# QCopterRC_ETH_Sch.net
KiCad netlist of a schematic drawn in Altium Designer
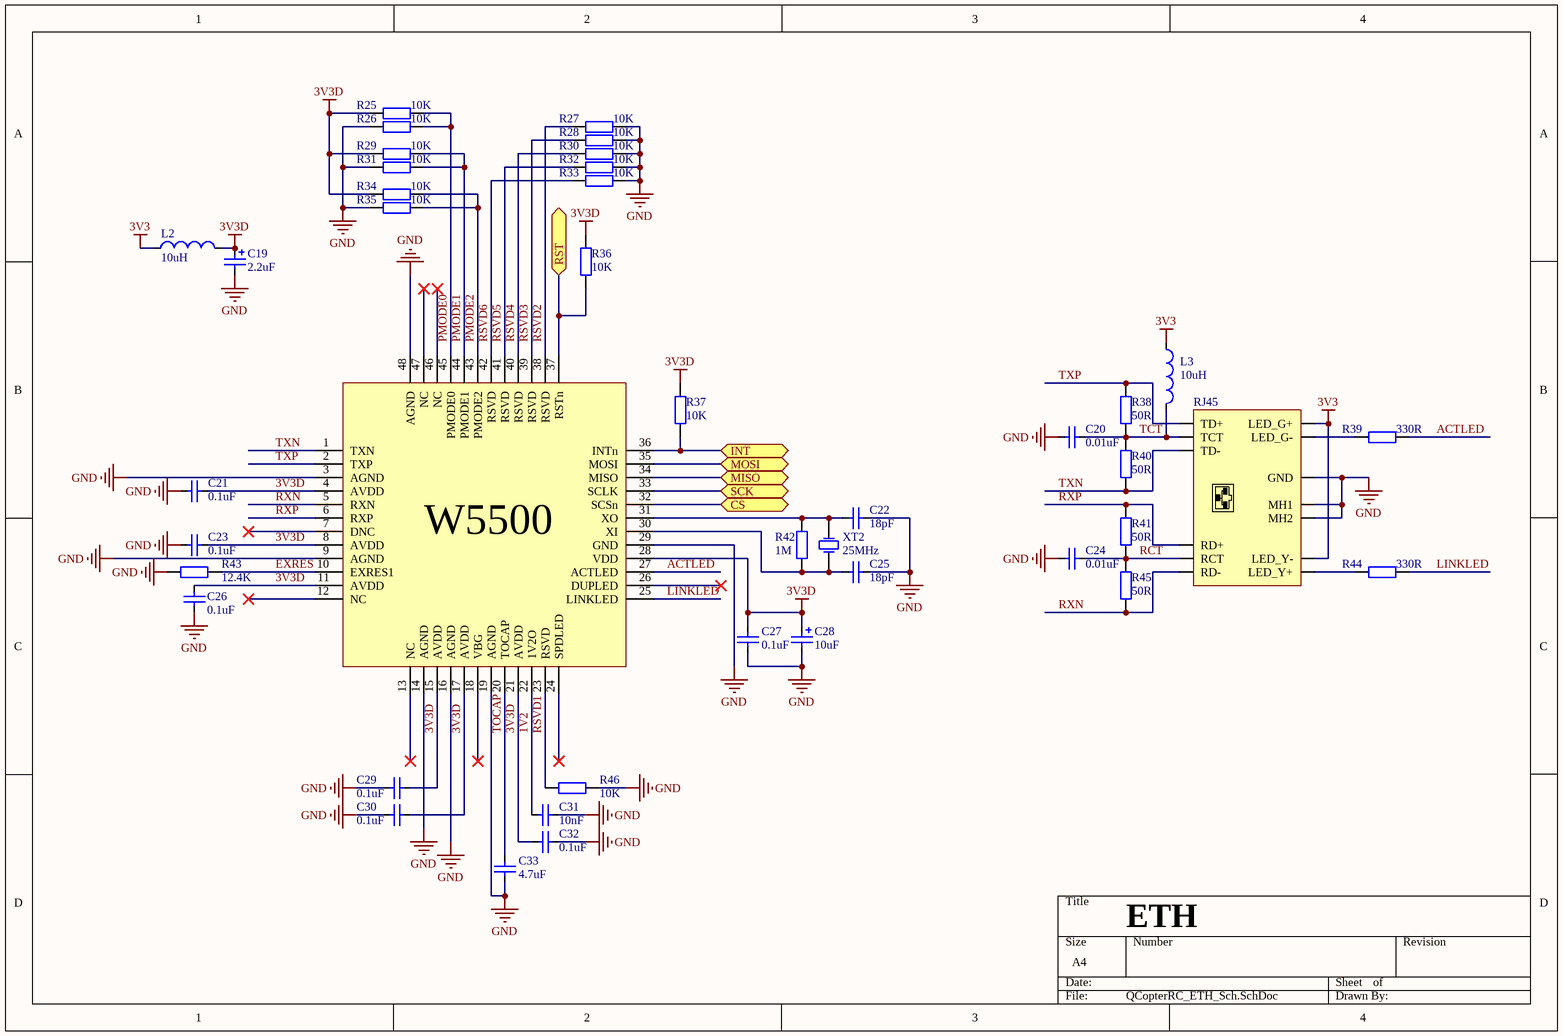
[diagram p0: QCopterRC_ETH_Sch.SchDoc]

(export (version "E")
  (design (tool "Eeschema 10.0.6"))
  (components
    (comp (ref "C19")
      (value "2.2uF")
      (footprint "PCB_Passive:CAP_TAN_P0805")
      (description "Capacitor")
      (fields (field (name "Comment") "Cap_Tan_0805"))
      (libsource (lib "SCH_Passive") (part "Cap_Tan_0805"))
    )
    (comp (ref "C20")
      (value "0.01uF")
      (footprint "PCB_Passive:CAP_0603")
      (description "Capacitor")
      (fields (field (name "Comment") "Cap_0603"))
      (libsource (lib "SCH_Passive") (part "Cap_0603"))
    )
    (comp (ref "C21")
      (value "0.1uF")
      (footprint "PCB_Passive:CAP_0603")
      (description "Capacitor")
      (fields (field (name "Comment") "Cap_0603"))
      (libsource (lib "SCH_Passive") (part "Cap_0603"))
    )
    (comp (ref "C22")
      (value "18pF")
      (footprint "PCB_Passive:CAP_0603")
      (description "Capacitor")
      (fields (field (name "Comment") "Cap_0603"))
      (libsource (lib "SCH_Passive") (part "Cap_0603"))
    )
    (comp (ref "C23")
      (value "0.1uF")
      (footprint "PCB_Passive:CAP_0603")
      (description "Capacitor")
      (fields (field (name "Comment") "Cap_0603"))
      (libsource (lib "SCH_Passive") (part "Cap_0603"))
    )
    (comp (ref "C24")
      (value "0.01uF")
      (footprint "PCB_Passive:CAP_0603")
      (description "Capacitor")
      (fields (field (name "Comment") "Cap_0603"))
      (libsource (lib "SCH_Passive") (part "Cap_0603"))
    )
    (comp (ref "C25")
      (value "18pF")
      (footprint "PCB_Passive:CAP_0603")
      (description "Capacitor")
      (fields (field (name "Comment") "Cap_0603"))
      (libsource (lib "SCH_Passive") (part "Cap_0603"))
    )
    (comp (ref "C26")
      (value "0.1uF")
      (footprint "PCB_Passive:CAP_0603")
      (description "Capacitor")
      (fields (field (name "Comment") "Cap_0603"))
      (libsource (lib "SCH_Passive") (part "Cap_0603"))
    )
    (comp (ref "C27")
      (value "0.1uF")
      (footprint "PCB_Passive:CAP_0603")
      (description "Capacitor")
      (fields (field (name "Comment") "Cap_0603"))
      (libsource (lib "SCH_Passive") (part "Cap_0603"))
    )
    (comp (ref "C28")
      (value "10uF")
      (footprint "PCB_Passive:CAP_TAN_B1210")
      (description "Capacitor")
      (fields (field (name "Comment") "Cap_Tan_1210"))
      (libsource (lib "SCH_Passive") (part "Cap_Tan_1210"))
    )
    (comp (ref "C29")
      (value "0.1uF")
      (footprint "PCB_Passive:CAP_0603")
      (description "Capacitor")
      (fields (field (name "Comment") "Cap_0603"))
      (libsource (lib "SCH_Passive") (part "Cap_0603"))
    )
    (comp (ref "C30")
      (value "0.1uF")
      (footprint "PCB_Passive:CAP_0603")
      (description "Capacitor")
      (fields (field (name "Comment") "Cap_0603"))
      (libsource (lib "SCH_Passive") (part "Cap_0603"))
    )
    (comp (ref "C31")
      (value "10nF")
      (footprint "PCB_Passive:CAP_0603")
      (description "Capacitor")
      (fields (field (name "Comment") "Cap_0603"))
      (libsource (lib "SCH_Passive") (part "Cap_0603"))
    )
    (comp (ref "C32")
      (value "0.1uF")
      (footprint "PCB_Passive:CAP_0603")
      (description "Capacitor")
      (fields (field (name "Comment") "Cap_0603"))
      (libsource (lib "SCH_Passive") (part "Cap_0603"))
    )
    (comp (ref "C33")
      (value "4.7uF")
      (footprint "PCB_Passive:CAP_0603")
      (description "Capacitor")
      (fields (field (name "Comment") "Cap_0603"))
      (libsource (lib "SCH_Passive") (part "Cap_0603"))
    )
    (comp (ref "L2")
      (value "10uH")
      (footprint "PCB_Passive:IND_0603")
      (description "Inductor")
      (fields (field (name "Comment") "Ind_0603"))
      (libsource (lib "SCH_Passive") (part "Ind_0603"))
    )
    (comp (ref "L3")
      (value "10uH")
      (footprint "PCB_Passive:IND_0603")
      (description "Inductor")
      (fields (field (name "Comment") "Ind_0603"))
      (libsource (lib "SCH_Passive") (part "Ind_0603"))
    )
    (comp (ref "R25")
      (value "10K")
      (footprint "PCB_Passive:RES_0603")
      (description "Resistor")
      (fields (field (name "Comment") "Res_0603"))
      (libsource (lib "SCH_Passive") (part "Res_0603"))
    )
    (comp (ref "R26")
      (value "10K")
      (footprint "PCB_Passive:RES_0603")
      (description "Resistor")
      (fields (field (name "Comment") "Res_0603"))
      (libsource (lib "SCH_Passive") (part "Res_0603"))
    )
    (comp (ref "R27")
      (value "10K")
      (footprint "PCB_Passive:RES_0603")
      (description "Resistor")
      (fields (field (name "Comment") "Res_0603"))
      (libsource (lib "SCH_Passive") (part "Res_0603"))
    )
    (comp (ref "R28")
      (value "10K")
      (footprint "PCB_Passive:RES_0603")
      (description "Resistor")
      (fields (field (name "Comment") "Res_0603"))
      (libsource (lib "SCH_Passive") (part "Res_0603"))
    )
    (comp (ref "R29")
      (value "10K")
      (footprint "PCB_Passive:RES_0603")
      (description "Resistor")
      (fields (field (name "Comment") "Res_0603"))
      (libsource (lib "SCH_Passive") (part "Res_0603"))
    )
    (comp (ref "R30")
      (value "10K")
      (footprint "PCB_Passive:RES_0603")
      (description "Resistor")
      (fields (field (name "Comment") "Res_0603"))
      (libsource (lib "SCH_Passive") (part "Res_0603"))
    )
    (comp (ref "R31")
      (value "10K")
      (footprint "PCB_Passive:RES_0603")
      (description "Resistor")
      (fields (field (name "Comment") "Res_0603"))
      (libsource (lib "SCH_Passive") (part "Res_0603"))
    )
    (comp (ref "R32")
      (value "10K")
      (footprint "PCB_Passive:RES_0603")
      (description "Resistor")
      (fields (field (name "Comment") "Res_0603"))
      (libsource (lib "SCH_Passive") (part "Res_0603"))
    )
    (comp (ref "R33")
      (value "10K")
      (footprint "PCB_Passive:RES_0603")
      (description "Resistor")
      (fields (field (name "Comment") "Res_0603"))
      (libsource (lib "SCH_Passive") (part "Res_0603"))
    )
    (comp (ref "R34")
      (value "10K")
      (footprint "PCB_Passive:RES_0603")
      (description "Resistor")
      (fields (field (name "Comment") "Res_0603"))
      (libsource (lib "SCH_Passive") (part "Res_0603"))
    )
    (comp (ref "R35")
      (value "10K")
      (footprint "PCB_Passive:RES_0603")
      (description "Resistor")
      (fields (field (name "Comment") "Res_0603"))
      (libsource (lib "SCH_Passive") (part "Res_0603"))
    )
    (comp (ref "R36")
      (value "10K")
      (footprint "PCB_Passive:RES_0603")
      (description "Resistor")
      (fields (field (name "Comment") "Res_0603"))
      (libsource (lib "") (part "Res_0603_1"))
    )
    (comp (ref "R37")
      (value "10K")
      (footprint "PCB_Passive:RES_0603")
      (description "Resistor")
      (fields (field (name "Comment") "Res_0603"))
      (libsource (lib "") (part "Res_0603_1"))
    )
    (comp (ref "R38")
      (value "50R")
      (footprint "PCB_Passive:RES_0603")
      (description "Resistor")
      (fields (field (name "Comment") "Res_0603"))
      (libsource (lib "") (part "Res_0603_1"))
    )
    (comp (ref "R39")
      (value "330R")
      (footprint "PCB_Passive:RES_0603")
      (description "Resistor")
      (fields (field (name "Comment") "Res_0603"))
      (libsource (lib "SCH_Passive") (part "Res_0603"))
    )
    (comp (ref "R40")
      (value "50R")
      (footprint "PCB_Passive:RES_0603")
      (description "Resistor")
      (fields (field (name "Comment") "Res_0603"))
      (libsource (lib "") (part "Res_0603_1"))
    )
    (comp (ref "R41")
      (value "50R")
      (footprint "PCB_Passive:RES_0603")
      (description "Resistor")
      (fields (field (name "Comment") "Res_0603"))
      (libsource (lib "") (part "Res_0603_1"))
    )
    (comp (ref "R42")
      (value "1M")
      (footprint "PCB_Passive:RES_0603")
      (description "Resistor")
      (fields (field (name "Comment") "Res_0603"))
      (libsource (lib "") (part "Res_0603_1"))
    )
    (comp (ref "R43")
      (value "12.4K")
      (footprint "PCB_Passive:RES_0603")
      (description "Resistor")
      (fields (field (name "Comment") "Res_0603"))
      (libsource (lib "SCH_Passive") (part "Res_0603"))
    )
    (comp (ref "R44")
      (value "330R")
      (footprint "PCB_Passive:RES_0603")
      (description "Resistor")
      (fields (field (name "Comment") "Res_0603"))
      (libsource (lib "SCH_Passive") (part "Res_0603"))
    )
    (comp (ref "R45")
      (value "50R")
      (footprint "PCB_Passive:RES_0603")
      (description "Resistor")
      (fields (field (name "Comment") "Res_0603"))
      (libsource (lib "") (part "Res_0603_1"))
    )
    (comp (ref "R46")
      (value "10K")
      (footprint "PCB_Passive:RES_0603")
      (description "Resistor")
      (fields (field (name "Comment") "Res_0603"))
      (libsource (lib "") (part "Res_0603_2"))
    )
    (comp (ref "RJ45")
      (value "RJ45")
      (footprint "PCB_Connector:RJ-45_LED")
      (description "ETH")
      (libsource (lib "SCH_Connector") (part "RJ45"))
    )
    (comp (ref "W5500")
      (value "W5500")
      (footprint "PCB_IC:W5500")
      (description "Ethernet")
      (libsource (lib "SCH_IC") (part "W5500"))
    )
    (comp (ref "XT2")
      (value "25MHz")
      (footprint "PCB_Oscillator:XTAL_5032")
      (description "Crystal Oscillator")
      (fields (field (name "Comment") "XTAL_5032") (field (name "PUBLISHER") "Altium Limited"))
      (libsource (lib "SCH_Oscillator") (part "XTAL_5032"))
    )
  )
  (nets
    (net (code "1") (name "/1V2") (class "Default")
      (node (ref "C31") (pin "2") (pinfunction "2_2") (pintype "passive"))
      (node (ref "W5500") (pin "22") (pinfunction "1V2O_22") (pintype "passive"))
    )
    (net (code "2") (name "/ACTLED") (class "Default")
      (node (ref "R39") (pin "1") (pinfunction "1_1") (pintype "passive"))
      (node (ref "W5500") (pin "27") (pinfunction "ACTLED_27") (pintype "passive"))
    )
    (net (code "3") (name "/CS") (class "Default")
      (node (ref "W5500") (pin "32") (pinfunction "SCSn_32") (pintype "passive"))
    )
    (net (code "5") (name "/EXRES") (class "Default")
      (node (ref "R43") (pin "1") (pinfunction "1_1") (pintype "passive"))
      (node (ref "W5500") (pin "10") (pinfunction "EXRES1_10") (pintype "passive"))
    )
    (net (code "6") (name "/INT") (class "Default")
      (node (ref "R37") (pin "1") (pinfunction "1_1") (pintype "passive"))
      (node (ref "W5500") (pin "36") (pinfunction "INTn_36") (pintype "passive"))
    )
    (net (code "7") (name "/LINKLED") (class "Default")
      (node (ref "R44") (pin "1") (pinfunction "1_1") (pintype "passive"))
      (node (ref "W5500") (pin "25") (pinfunction "LINKLED_25") (pintype "passive"))
    )
    (net (code "8") (name "/MISO") (class "Default")
      (node (ref "W5500") (pin "34") (pinfunction "MISO_34") (pintype "passive"))
    )
    (net (code "9") (name "/MOSI") (class "Default")
      (node (ref "W5500") (pin "35") (pinfunction "MOSI_35") (pintype "passive"))
    )
    (net (code "10") (name "/PMODE0") (class "Default")
      (node (ref "R25") (pin "1") (pinfunction "1_1") (pintype "passive"))
      (node (ref "R26") (pin "1") (pinfunction "1_1") (pintype "passive"))
      (node (ref "W5500") (pin "45") (pinfunction "PMODE0_45") (pintype "passive"))
    )
    (net (code "11") (name "/PMODE1") (class "Default")
      (node (ref "R29") (pin "1") (pinfunction "1_1") (pintype "passive"))
      (node (ref "R31") (pin "1") (pinfunction "1_1") (pintype "passive"))
      (node (ref "W5500") (pin "44") (pinfunction "PMODE1_44") (pintype "passive"))
    )
    (net (code "12") (name "/PMODE2") (class "Default")
      (node (ref "R34") (pin "1") (pinfunction "1_1") (pintype "passive"))
      (node (ref "R35") (pin "1") (pinfunction "1_1") (pintype "passive"))
      (node (ref "W5500") (pin "43") (pinfunction "PMODE2_43") (pintype "passive"))
    )
    (net (code "13") (name "/RCT") (class "Default")
      (node (ref "C24") (pin "2") (pinfunction "2_2") (pintype "passive"))
      (node (ref "R41") (pin "1") (pinfunction "1_1") (pintype "passive"))
      (node (ref "R45") (pin "2") (pinfunction "2_2") (pintype "passive"))
      (node (ref "RJ45") (pin "5") (pinfunction "RCT_5") (pintype "passive"))
    )
    (net (code "14") (name "/RST") (class "Default")
      (node (ref "R36") (pin "1") (pinfunction "1_1") (pintype "passive"))
      (node (ref "W5500") (pin "37") (pinfunction "RSTn_37") (pintype "passive"))
    )
    (net (code "15") (name "/RSVD1") (class "Default")
      (node (ref "R46") (pin "1") (pinfunction "1_1") (pintype "passive"))
      (node (ref "W5500") (pin "23") (pinfunction "RSVD_23") (pintype "passive"))
    )
    (net (code "16") (name "/RSVD2") (class "Default")
      (node (ref "R27") (pin "2") (pinfunction "2_2") (pintype "passive"))
      (node (ref "W5500") (pin "38") (pinfunction "RSVD_38") (pintype "passive"))
    )
    (net (code "17") (name "/RSVD3") (class "Default")
      (node (ref "R28") (pin "2") (pinfunction "2_2") (pintype "passive"))
      (node (ref "W5500") (pin "39") (pinfunction "RSVD_39") (pintype "passive"))
    )
    (net (code "18") (name "/RSVD4") (class "Default")
      (node (ref "R30") (pin "2") (pinfunction "2_2") (pintype "passive"))
      (node (ref "W5500") (pin "40") (pinfunction "RSVD_40") (pintype "passive"))
    )
    (net (code "19") (name "/RSVD5") (class "Default")
      (node (ref "R32") (pin "2") (pinfunction "2_2") (pintype "passive"))
      (node (ref "W5500") (pin "41") (pinfunction "RSVD_41") (pintype "passive"))
    )
    (net (code "20") (name "/RSVD6") (class "Default")
      (node (ref "R33") (pin "2") (pinfunction "2_2") (pintype "passive"))
      (node (ref "W5500") (pin "42") (pinfunction "RSVD_42") (pintype "passive"))
    )
    (net (code "21") (name "/RXN") (class "Default")
      (node (ref "R45") (pin "1") (pinfunction "1_1") (pintype "passive"))
      (node (ref "RJ45") (pin "6") (pinfunction "RD-_6") (pintype "passive"))
      (node (ref "W5500") (pin "5") (pinfunction "RXN_5") (pintype "passive"))
    )
    (net (code "22") (name "/RXP") (class "Default")
      (node (ref "R41") (pin "2") (pinfunction "2_2") (pintype "passive"))
      (node (ref "RJ45") (pin "3") (pinfunction "RD+_3") (pintype "passive"))
      (node (ref "W5500") (pin "6") (pinfunction "RXP_6") (pintype "passive"))
    )
    (net (code "23") (name "/SCK") (class "Default")
      (node (ref "W5500") (pin "33") (pinfunction "SCLK_33") (pintype "passive"))
    )
    (net (code "24") (name "/TCT") (class "Default")
      (node (ref "C20") (pin "2") (pinfunction "2_2") (pintype "passive"))
      (node (ref "L3") (pin "2") (pinfunction "2_2") (pintype "passive"))
      (node (ref "R38") (pin "1") (pinfunction "1_1") (pintype "passive"))
      (node (ref "R40") (pin "2") (pinfunction "2_2") (pintype "passive"))
      (node (ref "RJ45") (pin "4") (pinfunction "TCT_4") (pintype "passive"))
    )
    (net (code "25") (name "/TOCAP") (class "Default")
      (node (ref "C33") (pin "2") (pinfunction "2_2") (pintype "passive"))
      (node (ref "W5500") (pin "20") (pinfunction "TOCAP_20") (pintype "passive"))
    )
    (net (code "26") (name "/TXN") (class "Default")
      (node (ref "R40") (pin "1") (pinfunction "1_1") (pintype "passive"))
      (node (ref "RJ45") (pin "2") (pinfunction "TD-_2") (pintype "passive"))
      (node (ref "W5500") (pin "1") (pinfunction "TXN_1") (pintype "passive"))
    )
    (net (code "27") (name "/TXP") (class "Default")
      (node (ref "R38") (pin "2") (pinfunction "2_2") (pintype "passive"))
      (node (ref "RJ45") (pin "1") (pinfunction "TD+_1") (pintype "passive"))
      (node (ref "W5500") (pin "2") (pinfunction "TXP_2") (pintype "passive"))
    )
    (net (code "28") (name "3V3") (class "Default")
      (node (ref "L2") (pin "1") (pinfunction "1_1") (pintype "passive"))
      (node (ref "L3") (pin "1") (pinfunction "1_1") (pintype "passive"))
      (node (ref "RJ45") (pin "11") (pinfunction "LED_Y-_11") (pintype "passive"))
      (node (ref "RJ45") (pin "9") (pinfunction "LED_G+_9") (pintype "passive"))
    )
    (net (code "29") (name "3V3D") (class "Default")
      (node (ref "C19") (pin "1") (pinfunction "1_1") (pintype "passive"))
      (node (ref "C21") (pin "2") (pinfunction "2_2") (pintype "passive"))
      (node (ref "C23") (pin "2") (pinfunction "2_2") (pintype "passive"))
      (node (ref "C26") (pin "2") (pinfunction "2_2") (pintype "passive"))
      (node (ref "C27") (pin "2") (pinfunction "2_2") (pintype "passive"))
      (node (ref "C28") (pin "1") (pinfunction "1_1") (pintype "passive"))
      (node (ref "C29") (pin "1") (pinfunction "1_1") (pintype "passive"))
      (node (ref "C30") (pin "1") (pinfunction "1_1") (pintype "passive"))
      (node (ref "C32") (pin "2") (pinfunction "2_2") (pintype "passive"))
      (node (ref "L2") (pin "2") (pinfunction "2_2") (pintype "passive"))
      (node (ref "R25") (pin "2") (pinfunction "2_2") (pintype "passive"))
      (node (ref "R29") (pin "2") (pinfunction "2_2") (pintype "passive"))
      (node (ref "R34") (pin "2") (pinfunction "2_2") (pintype "passive"))
      (node (ref "R36") (pin "2") (pinfunction "2_2") (pintype "passive"))
      (node (ref "R37") (pin "2") (pinfunction "2_2") (pintype "passive"))
      (node (ref "W5500") (pin "11") (pinfunction "AVDD_11") (pintype "passive"))
      (node (ref "W5500") (pin "15") (pinfunction "AVDD_15") (pintype "passive"))
      (node (ref "W5500") (pin "17") (pinfunction "AVDD_17") (pintype "passive"))
      (node (ref "W5500") (pin "21") (pinfunction "AVDD_21") (pintype "passive"))
      (node (ref "W5500") (pin "28") (pinfunction "VDD_28") (pintype "passive"))
      (node (ref "W5500") (pin "4") (pinfunction "AVDD_4") (pintype "passive"))
      (node (ref "W5500") (pin "8") (pinfunction "AVDD_8") (pintype "passive"))
    )
    (net (code "30") (name "GND") (class "Default")
      (node (ref "C19") (pin "2") (pinfunction "2_2") (pintype "passive"))
      (node (ref "C20") (pin "1") (pinfunction "1_1") (pintype "passive"))
      (node (ref "C21") (pin "1") (pinfunction "1_1") (pintype "passive"))
      (node (ref "C22") (pin "1") (pinfunction "1_1") (pintype "passive"))
      (node (ref "C23") (pin "1") (pinfunction "1_1") (pintype "passive"))
      (node (ref "C24") (pin "1") (pinfunction "1_1") (pintype "passive"))
      (node (ref "C25") (pin "1") (pinfunction "1_1") (pintype "passive"))
      (node (ref "C26") (pin "1") (pinfunction "1_1") (pintype "passive"))
      (node (ref "C27") (pin "1") (pinfunction "1_1") (pintype "passive"))
      (node (ref "C28") (pin "2") (pinfunction "2_2") (pintype "passive"))
      (node (ref "C29") (pin "2") (pinfunction "2_2") (pintype "passive"))
      (node (ref "C30") (pin "2") (pinfunction "2_2") (pintype "passive"))
      (node (ref "C31") (pin "1") (pinfunction "1_1") (pintype "passive"))
      (node (ref "C32") (pin "1") (pinfunction "1_1") (pintype "passive"))
      (node (ref "C33") (pin "1") (pinfunction "1_1") (pintype "passive"))
      (node (ref "R26") (pin "2") (pinfunction "2_2") (pintype "passive"))
      (node (ref "R27") (pin "1") (pinfunction "1_1") (pintype "passive"))
      (node (ref "R28") (pin "1") (pinfunction "1_1") (pintype "passive"))
      (node (ref "R30") (pin "1") (pinfunction "1_1") (pintype "passive"))
      (node (ref "R31") (pin "2") (pinfunction "2_2") (pintype "passive"))
      (node (ref "R32") (pin "1") (pinfunction "1_1") (pintype "passive"))
      (node (ref "R33") (pin "1") (pinfunction "1_1") (pintype "passive"))
      (node (ref "R35") (pin "2") (pinfunction "2_2") (pintype "passive"))
      (node (ref "R43") (pin "2") (pinfunction "2_2") (pintype "passive"))
      (node (ref "R46") (pin "2") (pinfunction "2_2") (pintype "passive"))
      (node (ref "RJ45") (pin "13") (pinfunction "MH1_13") (pintype "passive"))
      (node (ref "RJ45") (pin "14") (pinfunction "MH2_14") (pintype "passive"))
      (node (ref "RJ45") (pin "8") (pinfunction "GND_8") (pintype "passive"))
      (node (ref "W5500") (pin "14") (pinfunction "AGND_14") (pintype "passive"))
      (node (ref "W5500") (pin "16") (pinfunction "AGND_16") (pintype "passive"))
      (node (ref "W5500") (pin "19") (pinfunction "AGND_19") (pintype "passive"))
      (node (ref "W5500") (pin "29") (pinfunction "GND_29") (pintype "passive"))
      (node (ref "W5500") (pin "3") (pinfunction "AGND_3") (pintype "passive"))
      (node (ref "W5500") (pin "48") (pinfunction "AGND_48") (pintype "passive"))
      (node (ref "W5500") (pin "9") (pinfunction "AGND_9") (pintype "passive"))
    )
    (net (code "31") (name "Net-(RJ45-LED_G-)") (class "Default")
      (node (ref "R39") (pin "2") (pinfunction "2_2") (pintype "passive"))
      (node (ref "RJ45") (pin "10") (pinfunction "LED_G-_10") (pintype "passive"))
    )
    (net (code "32") (name "Net-(RJ45-LED_Y+)") (class "Default")
      (node (ref "R44") (pin "2") (pinfunction "2_2") (pintype "passive"))
      (node (ref "RJ45") (pin "12") (pinfunction "LED_Y+_12") (pintype "passive"))
    )
    (net (code "33") (name "Net-(W5500-XI)") (class "Default")
      (node (ref "C25") (pin "2") (pinfunction "2_2") (pintype "passive"))
      (node (ref "R42") (pin "1") (pinfunction "1_1") (pintype "passive"))
      (node (ref "W5500") (pin "30") (pinfunction "XI_30") (pintype "passive"))
      (node (ref "XT2") (pin "1") (pinfunction "OSC1_1") (pintype "passive"))
    )
    (net (code "34") (name "Net-(W5500-XO)") (class "Default")
      (node (ref "C22") (pin "2") (pinfunction "2_2") (pintype "passive"))
      (node (ref "R42") (pin "2") (pinfunction "2_2") (pintype "passive"))
      (node (ref "W5500") (pin "31") (pinfunction "XO_31") (pintype "passive"))
      (node (ref "XT2") (pin "2") (pinfunction "OSC2_2") (pintype "passive"))
    )
    (net (code "35") (name "unconnected-(W5500-DNC-Pad7)") (class "Default")
      (node (ref "W5500") (pin "7") (pinfunction "DNC_7") (pintype "passive+no_connect"))
    )
    (net (code "36") (name "unconnected-(W5500-DUPLED-Pad26)") (class "Default")
      (node (ref "W5500") (pin "26") (pinfunction "DUPLED_26") (pintype "passive+no_connect"))
    )
    (net (code "37") (name "unconnected-(W5500-NC-Pad12)") (class "Default")
      (node (ref "W5500") (pin "12") (pinfunction "NC_12") (pintype "passive+no_connect"))
    )
    (net (code "38") (name "unconnected-(W5500-NC-Pad13)") (class "Default")
      (node (ref "W5500") (pin "13") (pinfunction "NC_13") (pintype "passive+no_connect"))
    )
    (net (code "39") (name "unconnected-(W5500-NC-Pad46)") (class "Default")
      (node (ref "W5500") (pin "46") (pinfunction "NC_46") (pintype "passive+no_connect"))
    )
    (net (code "40") (name "unconnected-(W5500-NC-Pad47)") (class "Default")
      (node (ref "W5500") (pin "47") (pinfunction "NC_47") (pintype "passive+no_connect"))
    )
    (net (code "41") (name "unconnected-(W5500-SPDLED-Pad24)") (class "Default")
      (node (ref "W5500") (pin "24") (pinfunction "SPDLED_24") (pintype "passive+no_connect"))
    )
    (net (code "42") (name "unconnected-(W5500-VBG-Pad18)") (class "Default")
      (node (ref "W5500") (pin "18") (pinfunction "VBG_18") (pintype "passive+no_connect"))
    )
  )
)
